# ninja-relay.net
KiCad netlist of a schematic drawn in EAGLE
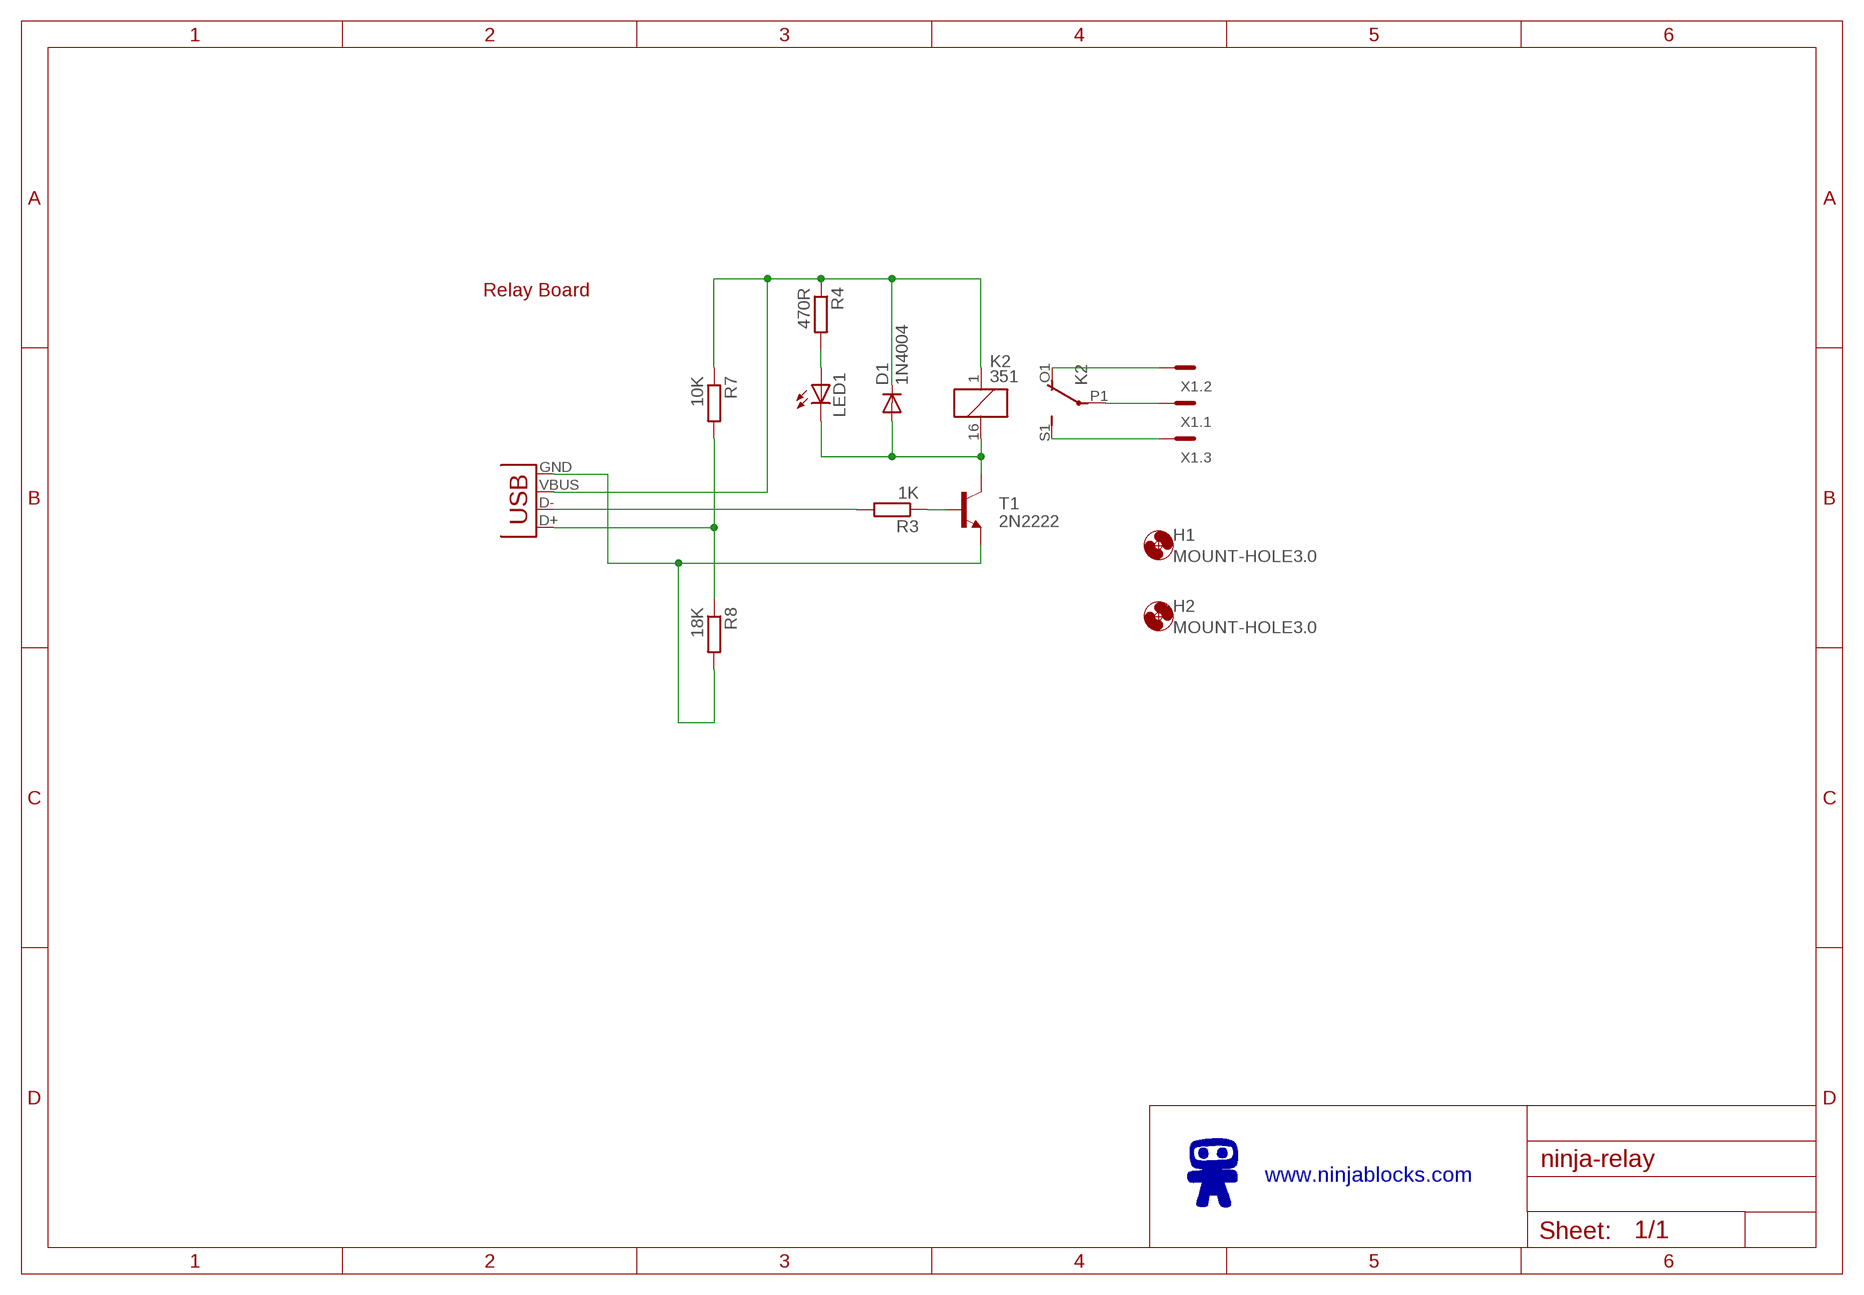
[diagram p0: schematic, sheet 1]

(export (version "E")
  (design (tool "Eeschema 10.0.6"))
  (components
    (comp (ref "D1")
      (value "1N4004")
      (footprint "eagle-import:DO41-10")
      (libsource (lib "eagle-import") (part "1N4004"))
    )
    (comp (ref "H1")
      (value "MOUNT-HOLE3.0")
      (footprint "eagle-import:3,0")
      (libsource (lib "eagle-import") (part "MOUNT-HOLE3.0"))
    )
    (comp (ref "H2")
      (value "MOUNT-HOLE3.0")
      (footprint "eagle-import:3,0")
      (libsource (lib "eagle-import") (part "MOUNT-HOLE3.0"))
    )
    (comp (ref "K2")
      (value "351")
      (footprint "eagle-import:351")
      (libsource (lib "eagle-import") (part "351"))
    )
    (comp (ref "LED1")
      (value "LED3MM")
      (footprint "eagle-import:LED3MM")
      (libsource (lib "eagle-import") (part "LED3MM"))
    )
    (comp (ref "R3")
      (value "1K")
      (footprint "eagle-import:0207_10")
      (libsource (lib "eagle-import") (part "R-EU_0207/10"))
    )
    (comp (ref "R4")
      (value "470R")
      (footprint "eagle-import:0207_10")
      (libsource (lib "eagle-import") (part "R-EU_0207/10"))
    )
    (comp (ref "R7")
      (value "10K")
      (footprint "eagle-import:0207_10")
      (libsource (lib "eagle-import") (part "R-EU_0207/10"))
    )
    (comp (ref "R8")
      (value "18K")
      (footprint "eagle-import:0207_10")
      (libsource (lib "eagle-import") (part "R-EU_0207/10"))
    )
    (comp (ref "T1")
      (value "2N2222")
      (footprint "eagle-import:TO92-EBC-OVAL")
      (libsource (lib "eagle-import") (part "2N2222"))
    )
    (comp (ref "X1")
      (value "MC3")
      (footprint "eagle-import:MC3")
      (libsource (lib "eagle-import") (part "MC3"))
    )
    (comp (ref "X2")
      (value "USB-A-H")
      (footprint "eagle-import:USB-A-H")
      (libsource (lib "eagle-import") (part "USB-A-H"))
    )
  )
  (nets
    (net (code "1") (name "Net-(D1-PadC)") (class "Default")
      (node (ref "D1") (pin "C") (pinfunction "C_C") (pintype "passive"))
      (node (ref "K2") (pin "1") (pinfunction "1_1") (pintype "passive"))
      (node (ref "R4") (pin "1") (pinfunction "1_1") (pintype "passive"))
      (node (ref "R7") (pin "1") (pinfunction "1_1") (pintype "passive"))
      (node (ref "X2") (pin "VBUS") (pinfunction "VBUS_VBUS") (pintype "bidirectional"))
    )
    (net (code "2") (name "Net-(K2A-2)") (class "Default")
      (node (ref "D1") (pin "A") (pinfunction "A_A") (pintype "passive"))
      (node (ref "K2") (pin "16") (pinfunction "2_16") (pintype "passive"))
      (node (ref "LED1") (pin "K") (pinfunction "C_K") (pintype "passive"))
      (node (ref "T1") (pin "C") (pinfunction "C_C") (pintype "passive"))
    )
    (net (code "3") (name "Net-(K2B-O)") (class "Default")
      (node (ref "K2") (pin "O1") (pinfunction "O_O1") (pintype "passive"))
      (node (ref "X1") (pin "2") (pinfunction "SK_2") (pintype "passive"))
    )
    (net (code "4") (name "Net-(K2B-P)") (class "Default")
      (node (ref "K2") (pin "P1") (pinfunction "P_P1") (pintype "passive"))
      (node (ref "X1") (pin "1") (pinfunction "SK_1") (pintype "passive"))
    )
    (net (code "5") (name "Net-(K2B-S)") (class "Default")
      (node (ref "K2") (pin "S1") (pinfunction "S_S1") (pintype "passive"))
      (node (ref "X1") (pin "3") (pinfunction "SK_3") (pintype "passive"))
    )
    (net (code "6") (name "Net-(LED1-PadA)") (class "Default")
      (node (ref "LED1") (pin "A") (pinfunction "A_A") (pintype "passive"))
      (node (ref "R4") (pin "2") (pinfunction "2_2") (pintype "passive"))
    )
    (net (code "7") (name "Net-(R3-Pad1)") (class "Default")
      (node (ref "R3") (pin "1") (pinfunction "1_1") (pintype "passive"))
      (node (ref "T1") (pin "B") (pinfunction "B_B") (pintype "passive"))
    )
    (net (code "8") (name "Net-(R3-Pad2)") (class "Default")
      (node (ref "R3") (pin "2") (pinfunction "2_2") (pintype "passive"))
      (node (ref "X2") (pin "D-") (pinfunction "D-_D-") (pintype "bidirectional"))
    )
    (net (code "9") (name "Net-(R7-Pad2)") (class "Default")
      (node (ref "R7") (pin "2") (pinfunction "2_2") (pintype "passive"))
      (node (ref "R8") (pin "1") (pinfunction "1_1") (pintype "passive"))
      (node (ref "X2") (pin "D+") (pinfunction "D+_D+") (pintype "bidirectional"))
    )
    (net (code "10") (name "Net-(R8-Pad2)") (class "Default")
      (node (ref "R8") (pin "2") (pinfunction "2_2") (pintype "passive"))
      (node (ref "T1") (pin "E") (pinfunction "E_E") (pintype "passive"))
      (node (ref "X2") (pin "GND") (pinfunction "GND_GND") (pintype "bidirectional"))
    )
  )
)
